# MUXBreakout_v8.net
KiCad netlist of a schematic drawn in EAGLE
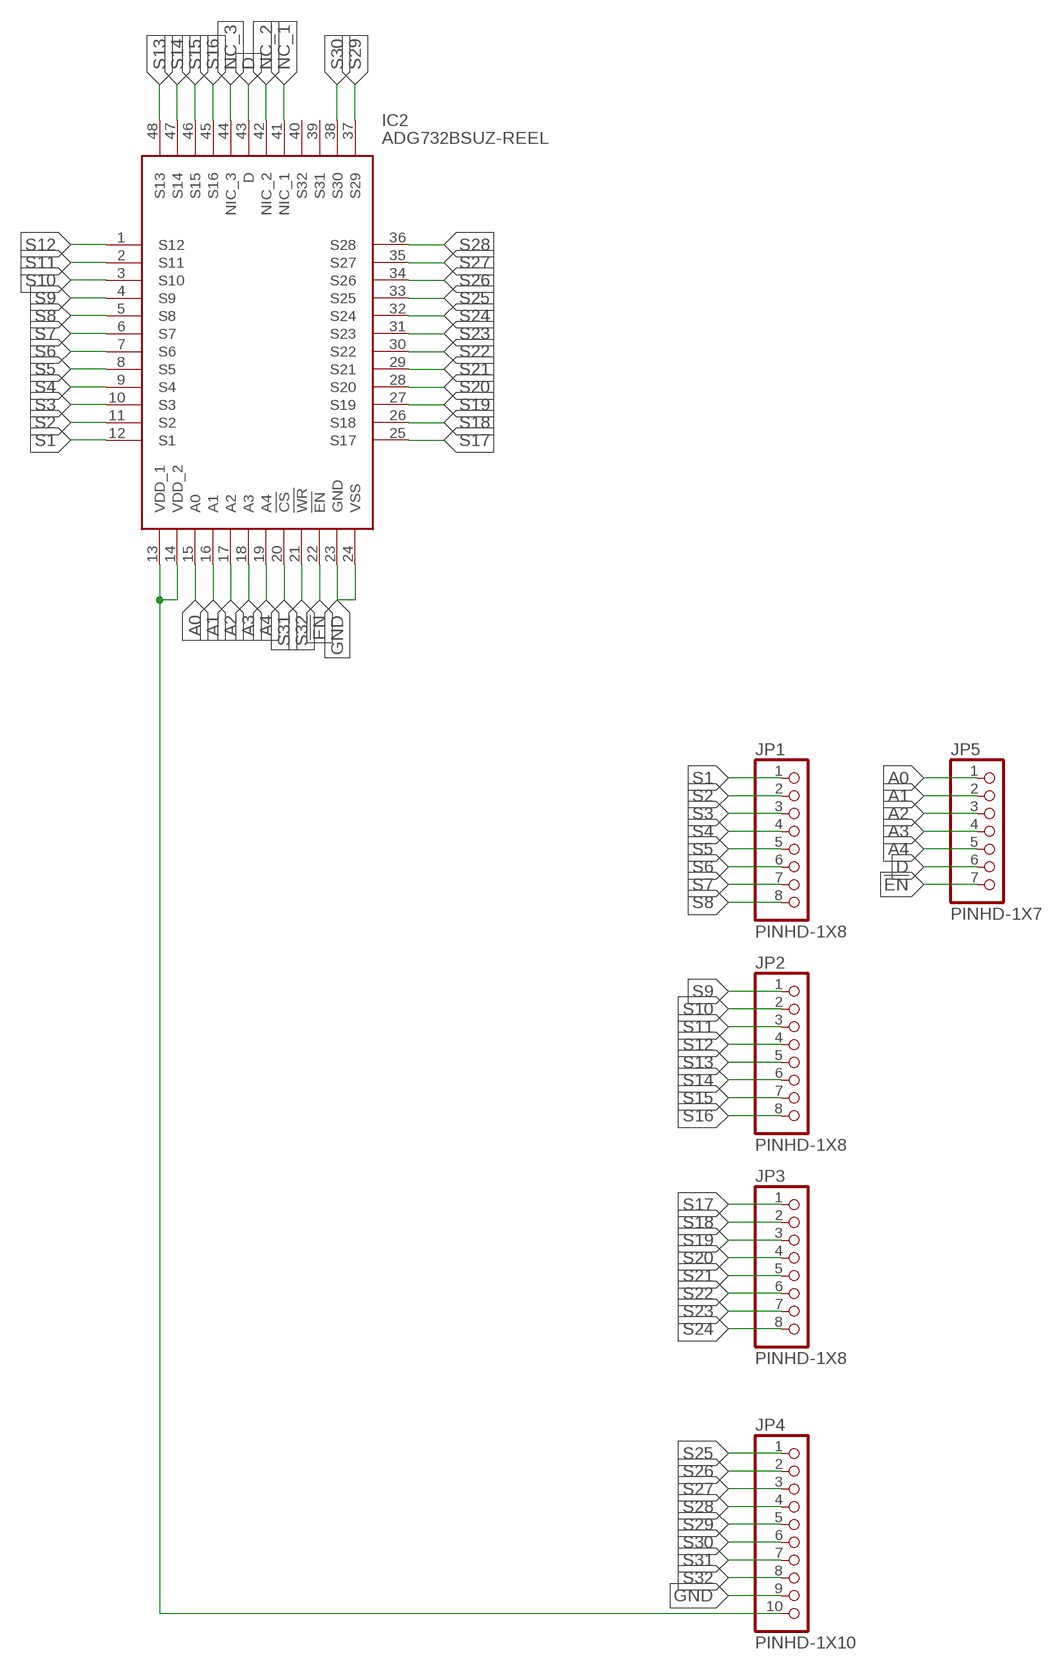
[diagram p0: schematic, sheet 1]

(export (version "E")
  (design (tool "Eeschema 10.0.6"))
  (components
    (comp (ref "IC2")
      (value "ADG732BSUZ-REEL")
      (footprint "eagle-import:QFP50P900X900X120-48N")
      (fields (field (name "MOUSER_PART_NUMBER") "584-ADG732BSUZ-R"))
      (libsource (lib "eagle-import") (part "ADG732BSUZ-REEL"))
    )
    (comp (ref "JP1")
      (value "PINHD-1X8")
      (footprint "eagle-import:1X08")
      (fields (field (name "MANUFACTURER") "Generic"))
      (libsource (lib "eagle-import") (part "PINHD-1X8"))
    )
    (comp (ref "JP2")
      (value "PINHD-1X8")
      (footprint "eagle-import:1X08")
      (fields (field (name "MANUFACTURER") "Generic"))
      (libsource (lib "eagle-import") (part "PINHD-1X8"))
    )
    (comp (ref "JP3")
      (value "PINHD-1X8")
      (footprint "eagle-import:1X08")
      (fields (field (name "MANUFACTURER") "Generic"))
      (libsource (lib "eagle-import") (part "PINHD-1X8"))
    )
    (comp (ref "JP4")
      (value "PINHD-1X10")
      (footprint "eagle-import:1X10")
      (fields (field (name "MANUFACTURER") "Generic"))
      (libsource (lib "eagle-import") (part "PINHD-1X10"))
    )
    (comp (ref "JP5")
      (value "PINHD-1X7")
      (footprint "eagle-import:1X07")
      (fields (field (name "MANUFACTURER") "Generic"))
      (libsource (lib "eagle-import") (part "PINHD-1X7"))
    )
  )
  (nets
    (net (code "1") (name "/~{EN}") (class "Default")
      (node (ref "IC2") (pin "22") (pinfunction "~{EN}_22") (pintype "bidirectional"))
      (node (ref "JP5") (pin "7") (pinfunction "7_7") (pintype "passive"))
    )
    (net (code "2") (name "A0") (class "Default")
      (node (ref "IC2") (pin "15") (pinfunction "A0_15") (pintype "bidirectional"))
      (node (ref "JP5") (pin "1") (pinfunction "1_1") (pintype "passive"))
    )
    (net (code "3") (name "A1") (class "Default")
      (node (ref "IC2") (pin "16") (pinfunction "A1_16") (pintype "bidirectional"))
      (node (ref "JP5") (pin "2") (pinfunction "2_2") (pintype "passive"))
    )
    (net (code "4") (name "A2") (class "Default")
      (node (ref "IC2") (pin "17") (pinfunction "A2_17") (pintype "bidirectional"))
      (node (ref "JP5") (pin "3") (pinfunction "3_3") (pintype "passive"))
    )
    (net (code "5") (name "A3") (class "Default")
      (node (ref "IC2") (pin "18") (pinfunction "A3_18") (pintype "bidirectional"))
      (node (ref "JP5") (pin "4") (pinfunction "4_4") (pintype "passive"))
    )
    (net (code "6") (name "A4") (class "Default")
      (node (ref "IC2") (pin "19") (pinfunction "A4_19") (pintype "bidirectional"))
      (node (ref "JP5") (pin "5") (pinfunction "5_5") (pintype "passive"))
    )
    (net (code "7") (name "D") (class "Default")
      (node (ref "IC2") (pin "43") (pinfunction "D_43") (pintype "bidirectional"))
      (node (ref "JP5") (pin "6") (pinfunction "6_6") (pintype "passive"))
    )
    (net (code "8") (name "GND") (class "Default")
      (node (ref "IC2") (pin "23") (pinfunction "GND_23") (pintype "bidirectional"))
      (node (ref "IC2") (pin "24") (pinfunction "VSS_24") (pintype "bidirectional"))
      (node (ref "JP4") (pin "9") (pinfunction "9_9") (pintype "passive"))
    )
    (net (code "9") (name "NC_1") (class "Default")
      (node (ref "IC2") (pin "41") (pinfunction "NIC_1_41") (pintype "bidirectional"))
    )
    (net (code "10") (name "NC_2") (class "Default")
      (node (ref "IC2") (pin "42") (pinfunction "NIC_2_42") (pintype "bidirectional"))
    )
    (net (code "11") (name "NC_3") (class "Default")
      (node (ref "IC2") (pin "44") (pinfunction "NIC_3_44") (pintype "bidirectional"))
    )
    (net (code "12") (name "Net-(IC2-VDD_1)") (class "Default")
      (node (ref "IC2") (pin "13") (pinfunction "VDD_1_13") (pintype "bidirectional"))
      (node (ref "IC2") (pin "14") (pinfunction "VDD_2_14") (pintype "bidirectional"))
      (node (ref "JP4") (pin "10") (pinfunction "10_10") (pintype "passive"))
    )
    (net (code "13") (name "S1") (class "Default")
      (node (ref "IC2") (pin "12") (pinfunction "S1_12") (pintype "bidirectional"))
      (node (ref "JP1") (pin "1") (pinfunction "1_1") (pintype "passive"))
    )
    (net (code "14") (name "S2") (class "Default")
      (node (ref "IC2") (pin "11") (pinfunction "S2_11") (pintype "bidirectional"))
      (node (ref "JP1") (pin "2") (pinfunction "2_2") (pintype "passive"))
    )
    (net (code "15") (name "S3") (class "Default")
      (node (ref "IC2") (pin "10") (pinfunction "S3_10") (pintype "bidirectional"))
      (node (ref "JP1") (pin "3") (pinfunction "3_3") (pintype "passive"))
    )
    (net (code "16") (name "S4") (class "Default")
      (node (ref "IC2") (pin "9") (pinfunction "S4_9") (pintype "bidirectional"))
      (node (ref "JP1") (pin "4") (pinfunction "4_4") (pintype "passive"))
    )
    (net (code "17") (name "S5") (class "Default")
      (node (ref "IC2") (pin "8") (pinfunction "S5_8") (pintype "bidirectional"))
      (node (ref "JP1") (pin "5") (pinfunction "5_5") (pintype "passive"))
    )
    (net (code "18") (name "S6") (class "Default")
      (node (ref "IC2") (pin "7") (pinfunction "S6_7") (pintype "bidirectional"))
      (node (ref "JP1") (pin "6") (pinfunction "6_6") (pintype "passive"))
    )
    (net (code "19") (name "S7") (class "Default")
      (node (ref "IC2") (pin "6") (pinfunction "S7_6") (pintype "bidirectional"))
      (node (ref "JP1") (pin "7") (pinfunction "7_7") (pintype "passive"))
    )
    (net (code "20") (name "S8") (class "Default")
      (node (ref "IC2") (pin "5") (pinfunction "S8_5") (pintype "bidirectional"))
      (node (ref "JP1") (pin "8") (pinfunction "8_8") (pintype "passive"))
    )
    (net (code "21") (name "S9") (class "Default")
      (node (ref "IC2") (pin "4") (pinfunction "S9_4") (pintype "bidirectional"))
      (node (ref "JP2") (pin "1") (pinfunction "1_1") (pintype "passive"))
    )
    (net (code "22") (name "S10") (class "Default")
      (node (ref "IC2") (pin "3") (pinfunction "S10_3") (pintype "bidirectional"))
      (node (ref "JP2") (pin "2") (pinfunction "2_2") (pintype "passive"))
    )
    (net (code "23") (name "S11") (class "Default")
      (node (ref "IC2") (pin "2") (pinfunction "S11_2") (pintype "bidirectional"))
      (node (ref "JP2") (pin "3") (pinfunction "3_3") (pintype "passive"))
    )
    (net (code "24") (name "S12") (class "Default")
      (node (ref "IC2") (pin "1") (pinfunction "S12_1") (pintype "bidirectional"))
      (node (ref "JP2") (pin "4") (pinfunction "4_4") (pintype "passive"))
    )
    (net (code "25") (name "S13") (class "Default")
      (node (ref "IC2") (pin "48") (pinfunction "S13_48") (pintype "bidirectional"))
      (node (ref "JP2") (pin "5") (pinfunction "5_5") (pintype "passive"))
    )
    (net (code "26") (name "S14") (class "Default")
      (node (ref "IC2") (pin "47") (pinfunction "S14_47") (pintype "bidirectional"))
      (node (ref "JP2") (pin "6") (pinfunction "6_6") (pintype "passive"))
    )
    (net (code "27") (name "S15") (class "Default")
      (node (ref "IC2") (pin "46") (pinfunction "S15_46") (pintype "bidirectional"))
      (node (ref "JP2") (pin "7") (pinfunction "7_7") (pintype "passive"))
    )
    (net (code "28") (name "S16") (class "Default")
      (node (ref "IC2") (pin "45") (pinfunction "S16_45") (pintype "bidirectional"))
      (node (ref "JP2") (pin "8") (pinfunction "8_8") (pintype "passive"))
    )
    (net (code "29") (name "S17") (class "Default")
      (node (ref "IC2") (pin "25") (pinfunction "S17_25") (pintype "bidirectional"))
      (node (ref "JP3") (pin "1") (pinfunction "1_1") (pintype "passive"))
    )
    (net (code "30") (name "S18") (class "Default")
      (node (ref "IC2") (pin "26") (pinfunction "S18_26") (pintype "bidirectional"))
      (node (ref "JP3") (pin "2") (pinfunction "2_2") (pintype "passive"))
    )
    (net (code "31") (name "S19") (class "Default")
      (node (ref "IC2") (pin "27") (pinfunction "S19_27") (pintype "bidirectional"))
      (node (ref "JP3") (pin "3") (pinfunction "3_3") (pintype "passive"))
    )
    (net (code "32") (name "S20") (class "Default")
      (node (ref "IC2") (pin "28") (pinfunction "S20_28") (pintype "bidirectional"))
      (node (ref "JP3") (pin "4") (pinfunction "4_4") (pintype "passive"))
    )
    (net (code "33") (name "S21") (class "Default")
      (node (ref "IC2") (pin "29") (pinfunction "S21_29") (pintype "bidirectional"))
      (node (ref "JP3") (pin "5") (pinfunction "5_5") (pintype "passive"))
    )
    (net (code "34") (name "S22") (class "Default")
      (node (ref "IC2") (pin "30") (pinfunction "S22_30") (pintype "bidirectional"))
      (node (ref "JP3") (pin "6") (pinfunction "6_6") (pintype "passive"))
    )
    (net (code "35") (name "S23") (class "Default")
      (node (ref "IC2") (pin "31") (pinfunction "S23_31") (pintype "bidirectional"))
      (node (ref "JP3") (pin "7") (pinfunction "7_7") (pintype "passive"))
    )
    (net (code "36") (name "S24") (class "Default")
      (node (ref "IC2") (pin "32") (pinfunction "S24_32") (pintype "bidirectional"))
      (node (ref "JP3") (pin "8") (pinfunction "8_8") (pintype "passive"))
    )
    (net (code "37") (name "S25") (class "Default")
      (node (ref "IC2") (pin "33") (pinfunction "S25_33") (pintype "bidirectional"))
      (node (ref "JP4") (pin "1") (pinfunction "1_1") (pintype "passive"))
    )
    (net (code "38") (name "S26") (class "Default")
      (node (ref "IC2") (pin "34") (pinfunction "S26_34") (pintype "bidirectional"))
      (node (ref "JP4") (pin "2") (pinfunction "2_2") (pintype "passive"))
    )
    (net (code "39") (name "S27") (class "Default")
      (node (ref "IC2") (pin "35") (pinfunction "S27_35") (pintype "bidirectional"))
      (node (ref "JP4") (pin "3") (pinfunction "3_3") (pintype "passive"))
    )
    (net (code "40") (name "S28") (class "Default")
      (node (ref "IC2") (pin "36") (pinfunction "S28_36") (pintype "bidirectional"))
      (node (ref "JP4") (pin "4") (pinfunction "4_4") (pintype "passive"))
    )
    (net (code "41") (name "S29") (class "Default")
      (node (ref "IC2") (pin "37") (pinfunction "S29_37") (pintype "bidirectional"))
      (node (ref "JP4") (pin "5") (pinfunction "5_5") (pintype "passive"))
    )
    (net (code "42") (name "S30") (class "Default")
      (node (ref "IC2") (pin "38") (pinfunction "S30_38") (pintype "bidirectional"))
      (node (ref "JP4") (pin "6") (pinfunction "6_6") (pintype "passive"))
    )
    (net (code "43") (name "S31") (class "Default")
      (node (ref "IC2") (pin "20") (pinfunction "~{CS}_20") (pintype "bidirectional"))
      (node (ref "JP4") (pin "7") (pinfunction "7_7") (pintype "passive"))
    )
    (net (code "44") (name "S32") (class "Default")
      (node (ref "IC2") (pin "21") (pinfunction "~{WR}_21") (pintype "bidirectional"))
      (node (ref "JP4") (pin "8") (pinfunction "8_8") (pintype "passive"))
    )
    (net (code "45") (name "unconnected-(IC2-S31-Pad39)") (class "Default")
      (node (ref "IC2") (pin "39") (pinfunction "S31_39") (pintype "bidirectional"))
    )
    (net (code "46") (name "unconnected-(IC2-S32-Pad40)") (class "Default")
      (node (ref "IC2") (pin "40") (pinfunction "S32_40") (pintype "bidirectional"))
    )
  )
)
